# rotaryEnc.net
KiCad netlist of a schematic drawn in EAGLE
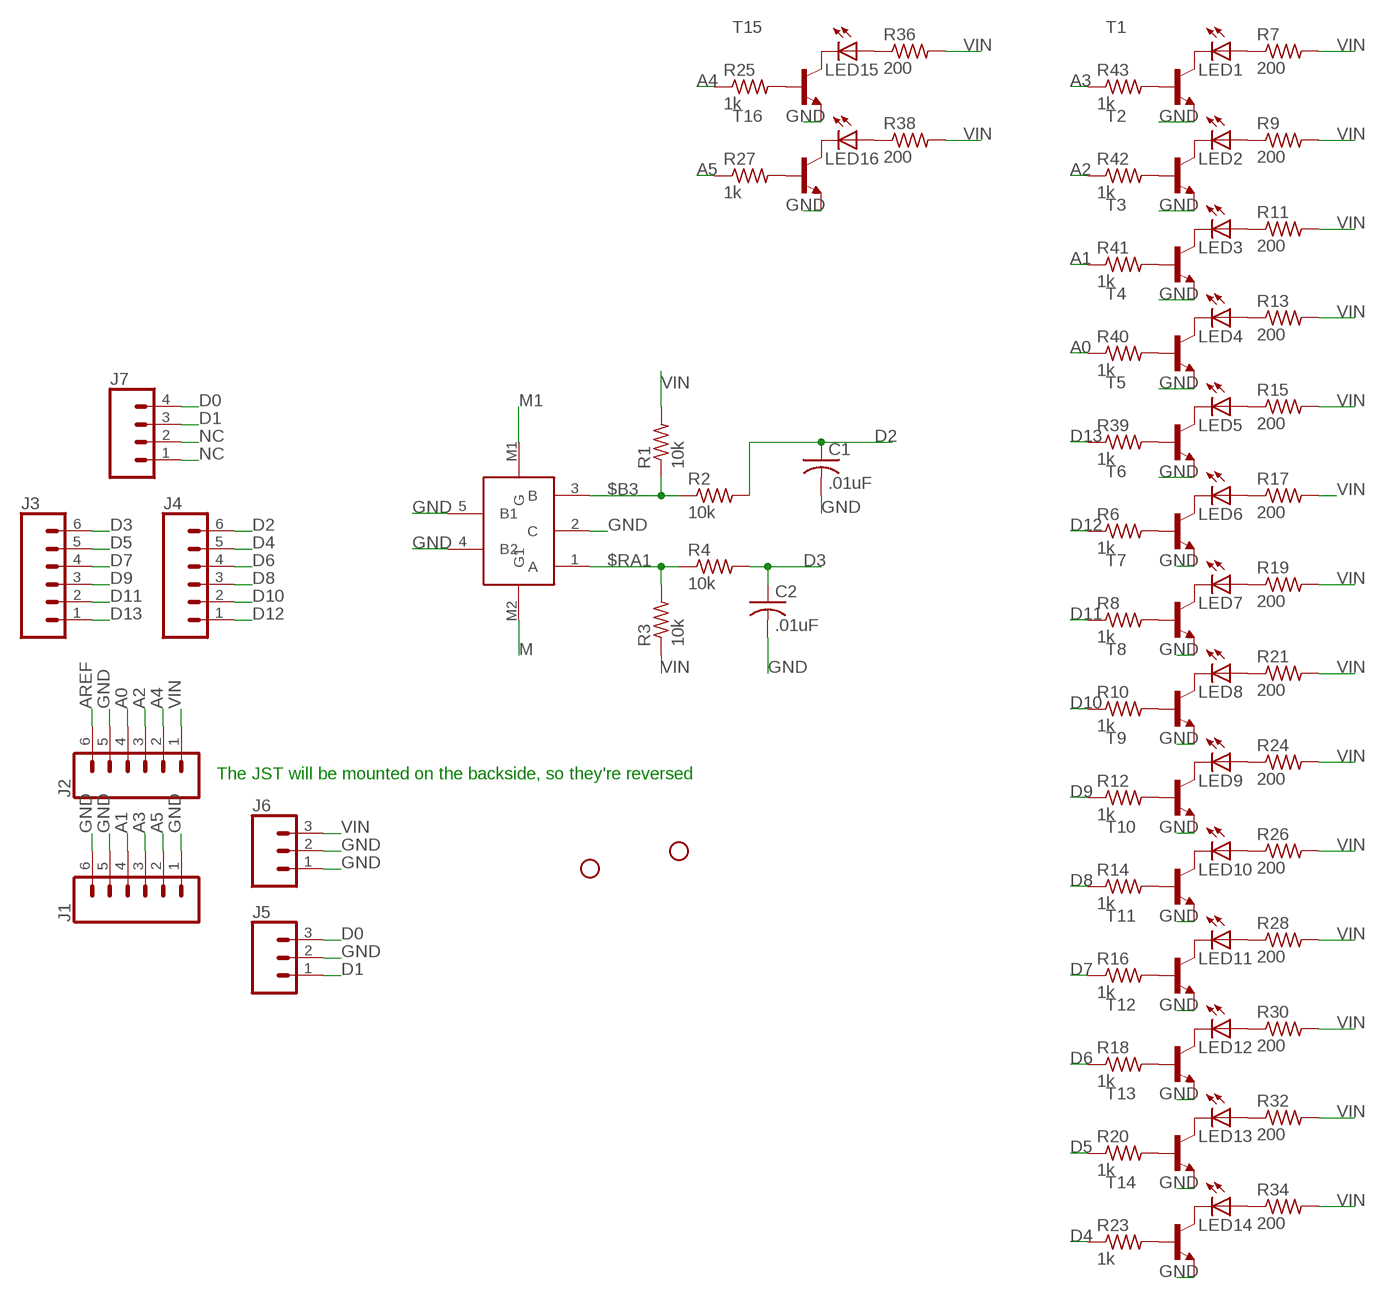
[diagram p0: schematic, sheet 1]

(export (version "E")
  (design (tool "Eeschema 10.0.6"))
  (components
    (comp (ref "C1")
      (value ".01uF")
      (footprint "eagle-import:C1206K")
      (libsource (lib "eagle-import") (part "C-USC1206K"))
    )
    (comp (ref "C2")
      (value ".01uF")
      (footprint "eagle-import:C1206K")
      (libsource (lib "eagle-import") (part "C-USC1206K"))
    )
    (comp (ref "H1")
      (value "STAND-OFF")
      (footprint "eagle-import:STAND-OFF")
      (libsource (lib "eagle-import") (part "STAND-OFF"))
    )
    (comp (ref "H2")
      (value "STAND-OFF")
      (footprint "eagle-import:STAND-OFF")
      (libsource (lib "eagle-import") (part "STAND-OFF"))
    )
    (comp (ref "J1")
      (value "CONN_061.27MM")
      (footprint "eagle-import:1X06_1.27MM")
      (libsource (lib "eagle-import") (part "CONN_061.27MM"))
    )
    (comp (ref "J2")
      (value "CONN_061.27MM")
      (footprint "eagle-import:1X06_1.27MM")
      (libsource (lib "eagle-import") (part "CONN_061.27MM"))
    )
    (comp (ref "J3")
      (value "CONN_061.27MM")
      (footprint "eagle-import:1X06_1.27MM")
      (libsource (lib "eagle-import") (part "CONN_061.27MM"))
    )
    (comp (ref "J4")
      (value "CONN_061.27MM")
      (footprint "eagle-import:1X06_1.27MM")
      (libsource (lib "eagle-import") (part "CONN_061.27MM"))
    )
    (comp (ref "J5")
      (value "CONN_03JST-PTH-VERT")
      (footprint "eagle-import:JST-3-PTH-VERT")
      (libsource (lib "eagle-import") (part "CONN_03JST-PTH-VERT"))
    )
    (comp (ref "J6")
      (value "CONN_03JST-PTH-VERT")
      (footprint "eagle-import:JST-3-PTH-VERT")
      (libsource (lib "eagle-import") (part "CONN_03JST-PTH-VERT"))
    )
    (comp (ref "J7")
      (value "CONN_041.27MM")
      (footprint "eagle-import:1X04_1.27MM")
      (libsource (lib "eagle-import") (part "CONN_041.27MM"))
    )
    (comp (ref "LED1")
      (value "LEDCHIP-LED0805")
      (footprint "eagle-import:CHIP-LED0805")
      (libsource (lib "eagle-import") (part "LEDCHIP-LED0805"))
    )
    (comp (ref "LED2")
      (value "LEDCHIP-LED0805")
      (footprint "eagle-import:CHIP-LED0805")
      (libsource (lib "eagle-import") (part "LEDCHIP-LED0805"))
    )
    (comp (ref "LED3")
      (value "LEDCHIP-LED0805")
      (footprint "eagle-import:CHIP-LED0805")
      (libsource (lib "eagle-import") (part "LEDCHIP-LED0805"))
    )
    (comp (ref "LED4")
      (value "LEDCHIP-LED0805")
      (footprint "eagle-import:CHIP-LED0805")
      (libsource (lib "eagle-import") (part "LEDCHIP-LED0805"))
    )
    (comp (ref "LED5")
      (value "LEDCHIP-LED0805")
      (footprint "eagle-import:CHIP-LED0805")
      (libsource (lib "eagle-import") (part "LEDCHIP-LED0805"))
    )
    (comp (ref "LED6")
      (value "LEDCHIP-LED0805")
      (footprint "eagle-import:CHIP-LED0805")
      (libsource (lib "eagle-import") (part "LEDCHIP-LED0805"))
    )
    (comp (ref "LED7")
      (value "LEDCHIP-LED0805")
      (footprint "eagle-import:CHIP-LED0805")
      (libsource (lib "eagle-import") (part "LEDCHIP-LED0805"))
    )
    (comp (ref "LED8")
      (value "LEDCHIP-LED0805")
      (footprint "eagle-import:CHIP-LED0805")
      (libsource (lib "eagle-import") (part "LEDCHIP-LED0805"))
    )
    (comp (ref "LED9")
      (value "LEDCHIP-LED0805")
      (footprint "eagle-import:CHIP-LED0805")
      (libsource (lib "eagle-import") (part "LEDCHIP-LED0805"))
    )
    (comp (ref "LED10")
      (value "LEDCHIP-LED0805")
      (footprint "eagle-import:CHIP-LED0805")
      (libsource (lib "eagle-import") (part "LEDCHIP-LED0805"))
    )
    (comp (ref "LED11")
      (value "LEDCHIP-LED0805")
      (footprint "eagle-import:CHIP-LED0805")
      (libsource (lib "eagle-import") (part "LEDCHIP-LED0805"))
    )
    (comp (ref "LED12")
      (value "LEDCHIP-LED0805")
      (footprint "eagle-import:CHIP-LED0805")
      (libsource (lib "eagle-import") (part "LEDCHIP-LED0805"))
    )
    (comp (ref "LED13")
      (value "LEDCHIP-LED0805")
      (footprint "eagle-import:CHIP-LED0805")
      (libsource (lib "eagle-import") (part "LEDCHIP-LED0805"))
    )
    (comp (ref "LED14")
      (value "LEDCHIP-LED0805")
      (footprint "eagle-import:CHIP-LED0805")
      (libsource (lib "eagle-import") (part "LEDCHIP-LED0805"))
    )
    (comp (ref "LED15")
      (value "LEDCHIP-LED0805")
      (footprint "eagle-import:CHIP-LED0805")
      (libsource (lib "eagle-import") (part "LEDCHIP-LED0805"))
    )
    (comp (ref "LED16")
      (value "LEDCHIP-LED0805")
      (footprint "eagle-import:CHIP-LED0805")
      (libsource (lib "eagle-import") (part "LEDCHIP-LED0805"))
    )
    (comp (ref "R1")
      (value "10k")
      (footprint "eagle-import:R0805")
      (libsource (lib "eagle-import") (part "R-US_R0805"))
    )
    (comp (ref "R2")
      (value "10k")
      (footprint "eagle-import:R0805")
      (libsource (lib "eagle-import") (part "R-US_R0805"))
    )
    (comp (ref "R3")
      (value "10k")
      (footprint "eagle-import:R0805")
      (libsource (lib "eagle-import") (part "R-US_R0805"))
    )
    (comp (ref "R4")
      (value "10k")
      (footprint "eagle-import:R0805")
      (libsource (lib "eagle-import") (part "R-US_R0805"))
    )
    (comp (ref "R6")
      (value "1k")
      (footprint "eagle-import:R0805")
      (libsource (lib "eagle-import") (part "R-US_R0805"))
    )
    (comp (ref "R7")
      (value "200")
      (footprint "eagle-import:R0805")
      (libsource (lib "eagle-import") (part "R-US_R0805"))
    )
    (comp (ref "R8")
      (value "1k")
      (footprint "eagle-import:R0805")
      (libsource (lib "eagle-import") (part "R-US_R0805"))
    )
    (comp (ref "R9")
      (value "200")
      (footprint "eagle-import:R0805")
      (libsource (lib "eagle-import") (part "R-US_R0805"))
    )
    (comp (ref "R10")
      (value "1k")
      (footprint "eagle-import:R0805")
      (libsource (lib "eagle-import") (part "R-US_R0805"))
    )
    (comp (ref "R11")
      (value "200")
      (footprint "eagle-import:R0805")
      (libsource (lib "eagle-import") (part "R-US_R0805"))
    )
    (comp (ref "R12")
      (value "1k")
      (footprint "eagle-import:R0805")
      (libsource (lib "eagle-import") (part "R-US_R0805"))
    )
    (comp (ref "R13")
      (value "200")
      (footprint "eagle-import:R0805")
      (libsource (lib "eagle-import") (part "R-US_R0805"))
    )
    (comp (ref "R14")
      (value "1k")
      (footprint "eagle-import:R0805")
      (libsource (lib "eagle-import") (part "R-US_R0805"))
    )
    (comp (ref "R15")
      (value "200")
      (footprint "eagle-import:R0805")
      (libsource (lib "eagle-import") (part "R-US_R0805"))
    )
    (comp (ref "R16")
      (value "1k")
      (footprint "eagle-import:R0805")
      (libsource (lib "eagle-import") (part "R-US_R0805"))
    )
    (comp (ref "R17")
      (value "200")
      (footprint "eagle-import:R0805")
      (libsource (lib "eagle-import") (part "R-US_R0805"))
    )
    (comp (ref "R18")
      (value "1k")
      (footprint "eagle-import:R0805")
      (libsource (lib "eagle-import") (part "R-US_R0805"))
    )
    (comp (ref "R19")
      (value "200")
      (footprint "eagle-import:R0805")
      (libsource (lib "eagle-import") (part "R-US_R0805"))
    )
    (comp (ref "R20")
      (value "1k")
      (footprint "eagle-import:R0805")
      (libsource (lib "eagle-import") (part "R-US_R0805"))
    )
    (comp (ref "R21")
      (value "200")
      (footprint "eagle-import:R0805")
      (libsource (lib "eagle-import") (part "R-US_R0805"))
    )
    (comp (ref "R23")
      (value "1k")
      (footprint "eagle-import:R0805")
      (libsource (lib "eagle-import") (part "R-US_R0805"))
    )
    (comp (ref "R24")
      (value "200")
      (footprint "eagle-import:R0805")
      (libsource (lib "eagle-import") (part "R-US_R0805"))
    )
    (comp (ref "R25")
      (value "1k")
      (footprint "eagle-import:R0805")
      (libsource (lib "eagle-import") (part "R-US_R0805"))
    )
    (comp (ref "R26")
      (value "200")
      (footprint "eagle-import:R0805")
      (libsource (lib "eagle-import") (part "R-US_R0805"))
    )
    (comp (ref "R27")
      (value "1k")
      (footprint "eagle-import:R0805")
      (libsource (lib "eagle-import") (part "R-US_R0805"))
    )
    (comp (ref "R28")
      (value "200")
      (footprint "eagle-import:R0805")
      (libsource (lib "eagle-import") (part "R-US_R0805"))
    )
    (comp (ref "R30")
      (value "200")
      (footprint "eagle-import:R0805")
      (libsource (lib "eagle-import") (part "R-US_R0805"))
    )
    (comp (ref "R32")
      (value "200")
      (footprint "eagle-import:R0805")
      (libsource (lib "eagle-import") (part "R-US_R0805"))
    )
    (comp (ref "R34")
      (value "200")
      (footprint "eagle-import:R0805")
      (libsource (lib "eagle-import") (part "R-US_R0805"))
    )
    (comp (ref "R36")
      (value "200")
      (footprint "eagle-import:R0805")
      (libsource (lib "eagle-import") (part "R-US_R0805"))
    )
    (comp (ref "R38")
      (value "200")
      (footprint "eagle-import:R0805")
      (libsource (lib "eagle-import") (part "R-US_R0805"))
    )
    (comp (ref "R39")
      (value "1k")
      (footprint "eagle-import:R0805")
      (libsource (lib "eagle-import") (part "R-US_R0805"))
    )
    (comp (ref "R40")
      (value "1k")
      (footprint "eagle-import:R0805")
      (libsource (lib "eagle-import") (part "R-US_R0805"))
    )
    (comp (ref "R41")
      (value "1k")
      (footprint "eagle-import:R0805")
      (libsource (lib "eagle-import") (part "R-US_R0805"))
    )
    (comp (ref "R42")
      (value "1k")
      (footprint "eagle-import:R0805")
      (libsource (lib "eagle-import") (part "R-US_R0805"))
    )
    (comp (ref "R43")
      (value "1k")
      (footprint "eagle-import:R0805")
      (libsource (lib "eagle-import") (part "R-US_R0805"))
    )
    (comp (ref "T1")
      (value "BCX56-NPN-SOT89-BCE")
      (footprint "eagle-import:SOT89-BCE")
      (libsource (lib "eagle-import") (part "-NPN-SOT89-BCEBCX56"))
    )
    (comp (ref "T2")
      (value "BCX56-NPN-SOT89-BCE")
      (footprint "eagle-import:SOT89-BCE")
      (libsource (lib "eagle-import") (part "-NPN-SOT89-BCEBCX56"))
    )
    (comp (ref "T3")
      (value "BCX56-NPN-SOT89-BCE")
      (footprint "eagle-import:SOT89-BCE")
      (libsource (lib "eagle-import") (part "-NPN-SOT89-BCEBCX56"))
    )
    (comp (ref "T4")
      (value "BCX56-NPN-SOT89-BCE")
      (footprint "eagle-import:SOT89-BCE")
      (libsource (lib "eagle-import") (part "-NPN-SOT89-BCEBCX56"))
    )
    (comp (ref "T5")
      (value "BCX56-NPN-SOT89-BCE")
      (footprint "eagle-import:SOT89-BCE")
      (libsource (lib "eagle-import") (part "-NPN-SOT89-BCEBCX56"))
    )
    (comp (ref "T6")
      (value "BCX56-NPN-SOT89-BCE")
      (footprint "eagle-import:SOT89-BCE")
      (libsource (lib "eagle-import") (part "-NPN-SOT89-BCEBCX56"))
    )
    (comp (ref "T7")
      (value "BCX56-NPN-SOT89-BCE")
      (footprint "eagle-import:SOT89-BCE")
      (libsource (lib "eagle-import") (part "-NPN-SOT89-BCEBCX56"))
    )
    (comp (ref "T8")
      (value "BCX56-NPN-SOT89-BCE")
      (footprint "eagle-import:SOT89-BCE")
      (libsource (lib "eagle-import") (part "-NPN-SOT89-BCEBCX56"))
    )
    (comp (ref "T9")
      (value "BCX56-NPN-SOT89-BCE")
      (footprint "eagle-import:SOT89-BCE")
      (libsource (lib "eagle-import") (part "-NPN-SOT89-BCEBCX56"))
    )
    (comp (ref "T10")
      (value "BCX56-NPN-SOT89-BCE")
      (footprint "eagle-import:SOT89-BCE")
      (libsource (lib "eagle-import") (part "-NPN-SOT89-BCEBCX56"))
    )
    (comp (ref "T11")
      (value "BCX56-NPN-SOT89-BCE")
      (footprint "eagle-import:SOT89-BCE")
      (libsource (lib "eagle-import") (part "-NPN-SOT89-BCEBCX56"))
    )
    (comp (ref "T12")
      (value "BCX56-NPN-SOT89-BCE")
      (footprint "eagle-import:SOT89-BCE")
      (libsource (lib "eagle-import") (part "-NPN-SOT89-BCEBCX56"))
    )
    (comp (ref "T13")
      (value "BCX56-NPN-SOT89-BCE")
      (footprint "eagle-import:SOT89-BCE")
      (libsource (lib "eagle-import") (part "-NPN-SOT89-BCEBCX56"))
    )
    (comp (ref "T14")
      (value "BCX56-NPN-SOT89-BCE")
      (footprint "eagle-import:SOT89-BCE")
      (libsource (lib "eagle-import") (part "-NPN-SOT89-BCEBCX56"))
    )
    (comp (ref "T15")
      (value "BCX56-NPN-SOT89-BCE")
      (footprint "eagle-import:SOT89-BCE")
      (libsource (lib "eagle-import") (part "-NPN-SOT89-BCEBCX56"))
    )
    (comp (ref "T16")
      (value "BCX56-NPN-SOT89-BCE")
      (footprint "eagle-import:SOT89-BCE")
      (libsource (lib "eagle-import") (part "-NPN-SOT89-BCEBCX56"))
    )
    (comp (ref "U$1")
      (value "EC11")
      (footprint "eagle-import:EC12")
      (libsource (lib "eagle-import") (part "EC11"))
    )
  )
  (nets
    (net (code "1") (name "/$B3") (class "Default")
      (node (ref "R1") (pin "1") (pinfunction "1_1") (pintype "passive"))
      (node (ref "R2") (pin "1") (pinfunction "1_1") (pintype "passive"))
      (node (ref "U$1") (pin "3") (pinfunction "B_3") (pintype "bidirectional"))
    )
    (net (code "2") (name "/$RA1") (class "Default")
      (node (ref "R3") (pin "2") (pinfunction "2_2") (pintype "passive"))
      (node (ref "R4") (pin "1") (pinfunction "1_1") (pintype "passive"))
      (node (ref "U$1") (pin "1") (pinfunction "A_1") (pintype "bidirectional"))
    )
    (net (code "3") (name "/A0") (class "Default")
      (node (ref "J2") (pin "4") (pinfunction "4_4") (pintype "passive"))
      (node (ref "R40") (pin "1") (pinfunction "1_1") (pintype "passive"))
    )
    (net (code "4") (name "/A1") (class "Default")
      (node (ref "J1") (pin "4") (pinfunction "4_4") (pintype "passive"))
      (node (ref "R41") (pin "1") (pinfunction "1_1") (pintype "passive"))
    )
    (net (code "5") (name "/A2") (class "Default")
      (node (ref "J2") (pin "3") (pinfunction "3_3") (pintype "passive"))
      (node (ref "R42") (pin "1") (pinfunction "1_1") (pintype "passive"))
    )
    (net (code "6") (name "/A3") (class "Default")
      (node (ref "J1") (pin "3") (pinfunction "3_3") (pintype "passive"))
      (node (ref "R43") (pin "1") (pinfunction "1_1") (pintype "passive"))
    )
    (net (code "7") (name "/A4") (class "Default")
      (node (ref "J2") (pin "2") (pinfunction "2_2") (pintype "passive"))
      (node (ref "R25") (pin "1") (pinfunction "1_1") (pintype "passive"))
    )
    (net (code "8") (name "/A5") (class "Default")
      (node (ref "J1") (pin "2") (pinfunction "2_2") (pintype "passive"))
      (node (ref "R27") (pin "1") (pinfunction "1_1") (pintype "passive"))
    )
    (net (code "9") (name "/AREF") (class "Default")
      (node (ref "J2") (pin "6") (pinfunction "6_6") (pintype "passive"))
    )
    (net (code "10") (name "/D0") (class "Default")
      (node (ref "J5") (pin "3") (pinfunction "3_3") (pintype "passive"))
      (node (ref "J7") (pin "4") (pinfunction "4_4") (pintype "passive"))
    )
    (net (code "11") (name "/D1") (class "Default")
      (node (ref "J5") (pin "1") (pinfunction "1_1") (pintype "passive"))
      (node (ref "J7") (pin "3") (pinfunction "3_3") (pintype "passive"))
    )
    (net (code "12") (name "/D2") (class "Default")
      (node (ref "C1") (pin "1") (pinfunction "1_1") (pintype "passive"))
      (node (ref "J4") (pin "6") (pinfunction "6_6") (pintype "passive"))
      (node (ref "R2") (pin "2") (pinfunction "2_2") (pintype "passive"))
    )
    (net (code "13") (name "/D3") (class "Default")
      (node (ref "C2") (pin "1") (pinfunction "1_1") (pintype "passive"))
      (node (ref "J3") (pin "6") (pinfunction "6_6") (pintype "passive"))
      (node (ref "R4") (pin "2") (pinfunction "2_2") (pintype "passive"))
    )
    (net (code "14") (name "/D4") (class "Default")
      (node (ref "J4") (pin "5") (pinfunction "5_5") (pintype "passive"))
      (node (ref "R23") (pin "1") (pinfunction "1_1") (pintype "passive"))
    )
    (net (code "15") (name "/D5") (class "Default")
      (node (ref "J3") (pin "5") (pinfunction "5_5") (pintype "passive"))
      (node (ref "R20") (pin "1") (pinfunction "1_1") (pintype "passive"))
    )
    (net (code "16") (name "/D6") (class "Default")
      (node (ref "J4") (pin "4") (pinfunction "4_4") (pintype "passive"))
      (node (ref "R18") (pin "1") (pinfunction "1_1") (pintype "passive"))
    )
    (net (code "17") (name "/D7") (class "Default")
      (node (ref "J3") (pin "4") (pinfunction "4_4") (pintype "passive"))
      (node (ref "R16") (pin "1") (pinfunction "1_1") (pintype "passive"))
    )
    (net (code "18") (name "/D8") (class "Default")
      (node (ref "J4") (pin "3") (pinfunction "3_3") (pintype "passive"))
      (node (ref "R14") (pin "1") (pinfunction "1_1") (pintype "passive"))
    )
    (net (code "19") (name "/D9") (class "Default")
      (node (ref "J3") (pin "3") (pinfunction "3_3") (pintype "passive"))
      (node (ref "R12") (pin "1") (pinfunction "1_1") (pintype "passive"))
    )
    (net (code "20") (name "/D10") (class "Default")
      (node (ref "J4") (pin "2") (pinfunction "2_2") (pintype "passive"))
      (node (ref "R10") (pin "1") (pinfunction "1_1") (pintype "passive"))
    )
    (net (code "21") (name "/D11") (class "Default")
      (node (ref "J3") (pin "2") (pinfunction "2_2") (pintype "passive"))
      (node (ref "R8") (pin "1") (pinfunction "1_1") (pintype "passive"))
    )
    (net (code "22") (name "/D12") (class "Default")
      (node (ref "J4") (pin "1") (pinfunction "1_1") (pintype "passive"))
      (node (ref "R6") (pin "1") (pinfunction "1_1") (pintype "passive"))
    )
    (net (code "23") (name "/D13") (class "Default")
      (node (ref "J3") (pin "1") (pinfunction "1_1") (pintype "passive"))
      (node (ref "R39") (pin "1") (pinfunction "1_1") (pintype "passive"))
    )
    (net (code "24") (name "/GND") (class "Default")
      (node (ref "C1") (pin "2") (pinfunction "2_2") (pintype "passive"))
      (node (ref "C2") (pin "2") (pinfunction "2_2") (pintype "passive"))
      (node (ref "J1") (pin "1") (pinfunction "1_1") (pintype "passive"))
      (node (ref "J1") (pin "5") (pinfunction "5_5") (pintype "passive"))
      (node (ref "J1") (pin "6") (pinfunction "6_6") (pintype "passive"))
      (node (ref "J2") (pin "5") (pinfunction "5_5") (pintype "passive"))
      (node (ref "J5") (pin "2") (pinfunction "2_2") (pintype "passive"))
      (node (ref "J6") (pin "1") (pinfunction "1_1") (pintype "passive"))
      (node (ref "J6") (pin "2") (pinfunction "2_2") (pintype "passive"))
      (node (ref "T1") (pin "E") (pinfunction "E_E") (pintype "passive"))
      (node (ref "T10") (pin "E") (pinfunction "E_E") (pintype "passive"))
      (node (ref "T11") (pin "E") (pinfunction "E_E") (pintype "passive"))
      (node (ref "T12") (pin "E") (pinfunction "E_E") (pintype "passive"))
      (node (ref "T13") (pin "E") (pinfunction "E_E") (pintype "passive"))
      (node (ref "T14") (pin "E") (pinfunction "E_E") (pintype "passive"))
      (node (ref "T15") (pin "E") (pinfunction "E_E") (pintype "passive"))
      (node (ref "T16") (pin "E") (pinfunction "E_E") (pintype "passive"))
      (node (ref "T2") (pin "E") (pinfunction "E_E") (pintype "passive"))
      (node (ref "T3") (pin "E") (pinfunction "E_E") (pintype "passive"))
      (node (ref "T4") (pin "E") (pinfunction "E_E") (pintype "passive"))
      (node (ref "T5") (pin "E") (pinfunction "E_E") (pintype "passive"))
      (node (ref "T6") (pin "E") (pinfunction "E_E") (pintype "passive"))
      (node (ref "T7") (pin "E") (pinfunction "E_E") (pintype "passive"))
      (node (ref "T8") (pin "E") (pinfunction "E_E") (pintype "passive"))
      (node (ref "T9") (pin "E") (pinfunction "E_E") (pintype "passive"))
      (node (ref "U$1") (pin "2") (pinfunction "C_2") (pintype "bidirectional"))
      (node (ref "U$1") (pin "4") (pinfunction "B2_4") (pintype "bidirectional"))
      (node (ref "U$1") (pin "5") (pinfunction "B1_5") (pintype "bidirectional"))
    )
    (net (code "25") (name "/M") (class "Default")
      (node (ref "U$1") (pin "M2") (pinfunction "G1_M2") (pintype "bidirectional"))
    )
    (net (code "26") (name "/M1") (class "Default")
      (node (ref "U$1") (pin "M1") (pinfunction "G_M1") (pintype "bidirectional"))
    )
    (net (code "27") (name "/NC") (class "Default")
      (node (ref "J7") (pin "1") (pinfunction "1_1") (pintype "passive"))
      (node (ref "J7") (pin "2") (pinfunction "2_2") (pintype "passive"))
    )
    (net (code "28") (name "/VIN") (class "Default")
      (node (ref "J2") (pin "1") (pinfunction "1_1") (pintype "passive"))
      (node (ref "J6") (pin "3") (pinfunction "3_3") (pintype "passive"))
      (node (ref "R1") (pin "2") (pinfunction "2_2") (pintype "passive"))
      (node (ref "R11") (pin "2") (pinfunction "2_2") (pintype "passive"))
      (node (ref "R13") (pin "2") (pinfunction "2_2") (pintype "passive"))
      (node (ref "R15") (pin "2") (pinfunction "2_2") (pintype "passive"))
      (node (ref "R17") (pin "2") (pinfunction "2_2") (pintype "passive"))
      (node (ref "R19") (pin "2") (pinfunction "2_2") (pintype "passive"))
      (node (ref "R21") (pin "2") (pinfunction "2_2") (pintype "passive"))
      (node (ref "R24") (pin "2") (pinfunction "2_2") (pintype "passive"))
      (node (ref "R26") (pin "2") (pinfunction "2_2") (pintype "passive"))
      (node (ref "R28") (pin "2") (pinfunction "2_2") (pintype "passive"))
      (node (ref "R3") (pin "1") (pinfunction "1_1") (pintype "passive"))
      (node (ref "R30") (pin "2") (pinfunction "2_2") (pintype "passive"))
      (node (ref "R32") (pin "2") (pinfunction "2_2") (pintype "passive"))
      (node (ref "R34") (pin "2") (pinfunction "2_2") (pintype "passive"))
      (node (ref "R36") (pin "2") (pinfunction "2_2") (pintype "passive"))
      (node (ref "R38") (pin "2") (pinfunction "2_2") (pintype "passive"))
      (node (ref "R7") (pin "2") (pinfunction "2_2") (pintype "passive"))
      (node (ref "R9") (pin "2") (pinfunction "2_2") (pintype "passive"))
    )
    (net (code "29") (name "Net-(LED1-PadA)") (class "Default")
      (node (ref "LED1") (pin "A") (pinfunction "A_A") (pintype "passive"))
      (node (ref "R7") (pin "1") (pinfunction "1_1") (pintype "passive"))
    )
    (net (code "30") (name "Net-(LED1-PadC)") (class "Default")
      (node (ref "LED1") (pin "C") (pinfunction "C_C") (pintype "passive"))
      (node (ref "T1") (pin "C") (pinfunction "C_C") (pintype "passive"))
    )
    (net (code "31") (name "Net-(LED2-PadA)") (class "Default")
      (node (ref "LED2") (pin "A") (pinfunction "A_A") (pintype "passive"))
      (node (ref "R9") (pin "1") (pinfunction "1_1") (pintype "passive"))
    )
    (net (code "32") (name "Net-(LED2-PadC)") (class "Default")
      (node (ref "LED2") (pin "C") (pinfunction "C_C") (pintype "passive"))
      (node (ref "T2") (pin "C") (pinfunction "C_C") (pintype "passive"))
    )
    (net (code "33") (name "Net-(LED3-PadA)") (class "Default")
      (node (ref "LED3") (pin "A") (pinfunction "A_A") (pintype "passive"))
      (node (ref "R11") (pin "1") (pinfunction "1_1") (pintype "passive"))
    )
    (net (code "34") (name "Net-(LED3-PadC)") (class "Default")
      (node (ref "LED3") (pin "C") (pinfunction "C_C") (pintype "passive"))
      (node (ref "T3") (pin "C") (pinfunction "C_C") (pintype "passive"))
    )
    (net (code "35") (name "Net-(LED4-PadA)") (class "Default")
      (node (ref "LED4") (pin "A") (pinfunction "A_A") (pintype "passive"))
      (node (ref "R13") (pin "1") (pinfunction "1_1") (pintype "passive"))
    )
    (net (code "36") (name "Net-(LED4-PadC)") (class "Default")
      (node (ref "LED4") (pin "C") (pinfunction "C_C") (pintype "passive"))
      (node (ref "T4") (pin "C") (pinfunction "C_C") (pintype "passive"))
    )
    (net (code "37") (name "Net-(LED5-PadA)") (class "Default")
      (node (ref "LED5") (pin "A") (pinfunction "A_A") (pintype "passive"))
      (node (ref "R15") (pin "1") (pinfunction "1_1") (pintype "passive"))
    )
    (net (code "38") (name "Net-(LED5-PadC)") (class "Default")
      (node (ref "LED5") (pin "C") (pinfunction "C_C") (pintype "passive"))
      (node (ref "T5") (pin "C") (pinfunction "C_C") (pintype "passive"))
    )
    (net (code "39") (name "Net-(LED6-PadA)") (class "Default")
      (node (ref "LED6") (pin "A") (pinfunction "A_A") (pintype "passive"))
      (node (ref "R17") (pin "1") (pinfunction "1_1") (pintype "passive"))
    )
    (net (code "40") (name "Net-(LED6-PadC)") (class "Default")
      (node (ref "LED6") (pin "C") (pinfunction "C_C") (pintype "passive"))
      (node (ref "T6") (pin "C") (pinfunction "C_C") (pintype "passive"))
    )
    (net (code "41") (name "Net-(LED7-PadA)") (class "Default")
      (node (ref "LED7") (pin "A") (pinfunction "A_A") (pintype "passive"))
      (node (ref "R19") (pin "1") (pinfunction "1_1") (pintype "passive"))
    )
    (net (code "42") (name "Net-(LED7-PadC)") (class "Default")
      (node (ref "LED7") (pin "C") (pinfunction "C_C") (pintype "passive"))
      (node (ref "T7") (pin "C") (pinfunction "C_C") (pintype "passive"))
    )
    (net (code "43") (name "Net-(LED8-PadA)") (class "Default")
      (node (ref "LED8") (pin "A") (pinfunction "A_A") (pintype "passive"))
      (node (ref "R21") (pin "1") (pinfunction "1_1") (pintype "passive"))
    )
    (net (code "44") (name "Net-(LED8-PadC)") (class "Default")
      (node (ref "LED8") (pin "C") (pinfunction "C_C") (pintype "passive"))
      (node (ref "T8") (pin "C") (pinfunction "C_C") (pintype "passive"))
    )
    (net (code "45") (name "Net-(LED9-PadA)") (class "Default")
      (node (ref "LED9") (pin "A") (pinfunction "A_A") (pintype "passive"))
      (node (ref "R24") (pin "1") (pinfunction "1_1") (pintype "passive"))
    )
    (net (code "46") (name "Net-(LED9-PadC)") (class "Default")
      (node (ref "LED9") (pin "C") (pinfunction "C_C") (pintype "passive"))
      (node (ref "T9") (pin "C") (pinfunction "C_C") (pintype "passive"))
    )
    (net (code "47") (name "Net-(LED10-PadA)") (class "Default")
      (node (ref "LED10") (pin "A") (pinfunction "A_A") (pintype "passive"))
      (node (ref "R26") (pin "1") (pinfunction "1_1") (pintype "passive"))
    )
    (net (code "48") (name "Net-(LED10-PadC)") (class "Default")
      (node (ref "LED10") (pin "C") (pinfunction "C_C") (pintype "passive"))
      (node (ref "T10") (pin "C") (pinfunction "C_C") (pintype "passive"))
    )
    (net (code "49") (name "Net-(LED11-PadA)") (class "Default")
      (node (ref "LED11") (pin "A") (pinfunction "A_A") (pintype "passive"))
      (node (ref "R28") (pin "1") (pinfunction "1_1") (pintype "passive"))
    )
    (net (code "50") (name "Net-(LED11-PadC)") (class "Default")
      (node (ref "LED11") (pin "C") (pinfunction "C_C") (pintype "passive"))
      (node (ref "T11") (pin "C") (pinfunction "C_C") (pintype "passive"))
    )
    (net (code "51") (name "Net-(LED12-PadA)") (class "Default")
      (node (ref "LED12") (pin "A") (pinfunction "A_A") (pintype "passive"))
      (node (ref "R30") (pin "1") (pinfunction "1_1") (pintype "passive"))
    )
    (net (code "52") (name "Net-(LED12-PadC)") (class "Default")
      (node (ref "LED12") (pin "C") (pinfunction "C_C") (pintype "passive"))
      (node (ref "T12") (pin "C") (pinfunction "C_C") (pintype "passive"))
    )
    (net (code "53") (name "Net-(LED13-PadA)") (class "Default")
      (node (ref "LED13") (pin "A") (pinfunction "A_A") (pintype "passive"))
      (node (ref "R32") (pin "1") (pinfunction "1_1") (pintype "passive"))
    )
    (net (code "54") (name "Net-(LED13-PadC)") (class "Default")
      (node (ref "LED13") (pin "C") (pinfunction "C_C") (pintype "passive"))
      (node (ref "T13") (pin "C") (pinfunction "C_C") (pintype "passive"))
    )
    (net (code "55") (name "Net-(LED14-PadA)") (class "Default")
      (node (ref "LED14") (pin "A") (pinfunction "A_A") (pintype "passive"))
      (node (ref "R34") (pin "1") (pinfunction "1_1") (pintype "passive"))
    )
    (net (code "56") (name "Net-(LED14-PadC)") (class "Default")
      (node (ref "LED14") (pin "C") (pinfunction "C_C") (pintype "passive"))
      (node (ref "T14") (pin "C") (pinfunction "C_C") (pintype "passive"))
    )
    (net (code "57") (name "Net-(LED15-PadA)") (class "Default")
      (node (ref "LED15") (pin "A") (pinfunction "A_A") (pintype "passive"))
      (node (ref "R36") (pin "1") (pinfunction "1_1") (pintype "passive"))
    )
    (net (code "58") (name "Net-(LED15-PadC)") (class "Default")
      (node (ref "LED15") (pin "C") (pinfunction "C_C") (pintype "passive"))
      (node (ref "T15") (pin "C") (pinfunction "C_C") (pintype "passive"))
    )
    (net (code "59") (name "Net-(LED16-PadA)") (class "Default")
      (node (ref "LED16") (pin "A") (pinfunction "A_A") (pintype "passive"))
      (node (ref "R38") (pin "1") (pinfunction "1_1") (pintype "passive"))
    )
    (net (code "60") (name "Net-(LED16-PadC)") (class "Default")
      (node (ref "LED16") (pin "C") (pinfunction "C_C") (pintype "passive"))
      (node (ref "T16") (pin "C") (pinfunction "C_C") (pintype "passive"))
    )
    (net (code "61") (name "Net-(R6-Pad2)") (class "Default")
      (node (ref "R6") (pin "2") (pinfunction "2_2") (pintype "passive"))
      (node (ref "T6") (pin "B") (pinfunction "B_B") (pintype "passive"))
    )
    (net (code "62") (name "Net-(R8-Pad2)") (class "Default")
      (node (ref "R8") (pin "2") (pinfunction "2_2") (pintype "passive"))
      (node (ref "T7") (pin "B") (pinfunction "B_B") (pintype "passive"))
    )
    (net (code "63") (name "Net-(R10-Pad2)") (class "Default")
      (node (ref "R10") (pin "2") (pinfunction "2_2") (pintype "passive"))
      (node (ref "T8") (pin "B") (pinfunction "B_B") (pintype "passive"))
    )
    (net (code "64") (name "Net-(R12-Pad2)") (class "Default")
      (node (ref "R12") (pin "2") (pinfunction "2_2") (pintype "passive"))
      (node (ref "T9") (pin "B") (pinfunction "B_B") (pintype "passive"))
    )
    (net (code "65") (name "Net-(R14-Pad2)") (class "Default")
      (node (ref "R14") (pin "2") (pinfunction "2_2") (pintype "passive"))
      (node (ref "T10") (pin "B") (pinfunction "B_B") (pintype "passive"))
    )
    (net (code "66") (name "Net-(R16-Pad2)") (class "Default")
      (node (ref "R16") (pin "2") (pinfunction "2_2") (pintype "passive"))
      (node (ref "T11") (pin "B") (pinfunction "B_B") (pintype "passive"))
    )
    (net (code "67") (name "Net-(R18-Pad2)") (class "Default")
      (node (ref "R18") (pin "2") (pinfunction "2_2") (pintype "passive"))
      (node (ref "T12") (pin "B") (pinfunction "B_B") (pintype "passive"))
    )
    (net (code "68") (name "Net-(R20-Pad2)") (class "Default")
      (node (ref "R20") (pin "2") (pinfunction "2_2") (pintype "passive"))
      (node (ref "T13") (pin "B") (pinfunction "B_B") (pintype "passive"))
    )
    (net (code "69") (name "Net-(R23-Pad2)") (class "Default")
      (node (ref "R23") (pin "2") (pinfunction "2_2") (pintype "passive"))
      (node (ref "T14") (pin "B") (pinfunction "B_B") (pintype "passive"))
    )
    (net (code "70") (name "Net-(R25-Pad2)") (class "Default")
      (node (ref "R25") (pin "2") (pinfunction "2_2") (pintype "passive"))
      (node (ref "T15") (pin "B") (pinfunction "B_B") (pintype "passive"))
    )
    (net (code "71") (name "Net-(R27-Pad2)") (class "Default")
      (node (ref "R27") (pin "2") (pinfunction "2_2") (pintype "passive"))
      (node (ref "T16") (pin "B") (pinfunction "B_B") (pintype "passive"))
    )
    (net (code "72") (name "Net-(R39-Pad2)") (class "Default")
      (node (ref "R39") (pin "2") (pinfunction "2_2") (pintype "passive"))
      (node (ref "T5") (pin "B") (pinfunction "B_B") (pintype "passive"))
    )
    (net (code "73") (name "Net-(R40-Pad2)") (class "Default")
      (node (ref "R40") (pin "2") (pinfunction "2_2") (pintype "passive"))
      (node (ref "T4") (pin "B") (pinfunction "B_B") (pintype "passive"))
    )
    (net (code "74") (name "Net-(R41-Pad2)") (class "Default")
      (node (ref "R41") (pin "2") (pinfunction "2_2") (pintype "passive"))
      (node (ref "T3") (pin "B") (pinfunction "B_B") (pintype "passive"))
    )
    (net (code "75") (name "Net-(R42-Pad2)") (class "Default")
      (node (ref "R42") (pin "2") (pinfunction "2_2") (pintype "passive"))
      (node (ref "T2") (pin "B") (pinfunction "B_B") (pintype "passive"))
    )
    (net (code "76") (name "Net-(R43-Pad2)") (class "Default")
      (node (ref "R43") (pin "2") (pinfunction "2_2") (pintype "passive"))
      (node (ref "T1") (pin "B") (pinfunction "B_B") (pintype "passive"))
    )
  )
)
